# complete_system.net
KiCad netlist of a schematic drawn in EAGLE
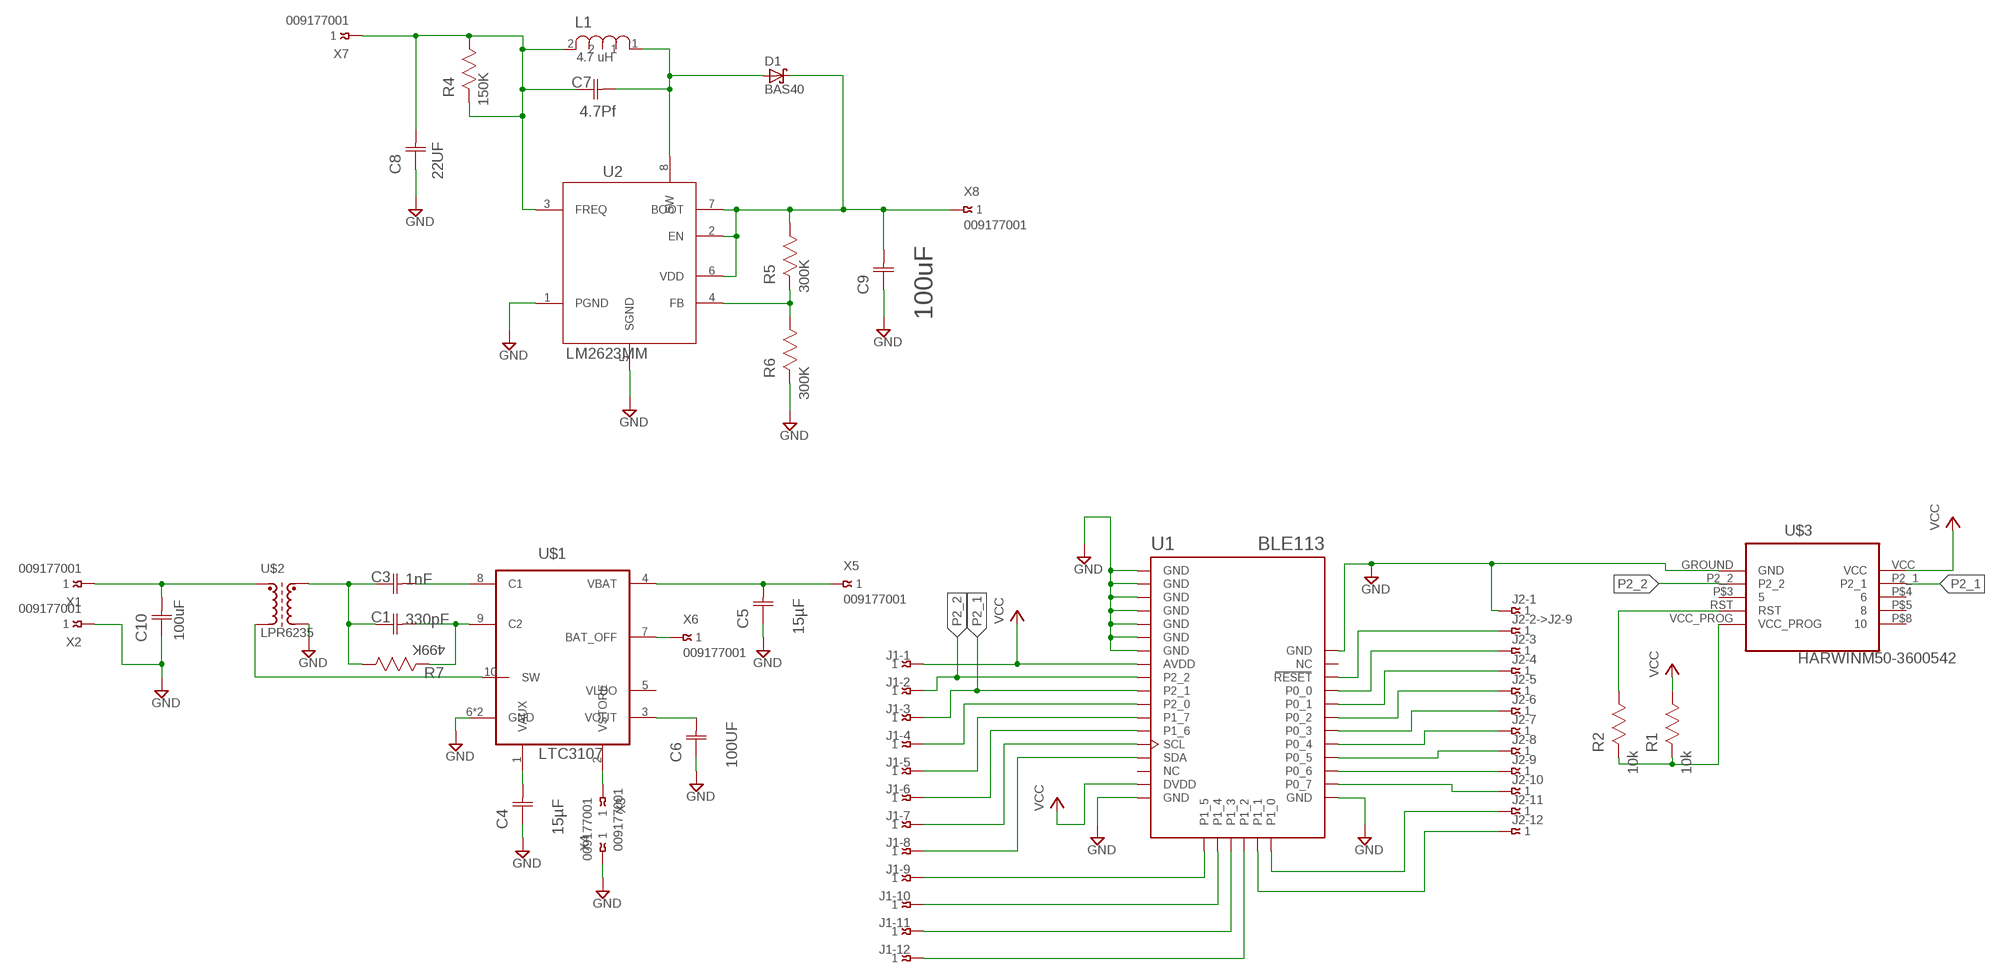
[diagram p0: schematic, sheet 1]

(export (version "E")
  (design (tool "Eeschema 10.0.6"))
  (components
    (comp (ref "C1")
      (value "330pF")
      (footprint "eagle-import:CAPC1005X60N")
      (fields (field (name "MPN") "0402YD105KAT2A") (field (name "TOLERANCE") "±10%"))
      (libsource (lib "eagle-import") (part "0402YD105KAT2A"))
    )
    (comp (ref "C3")
      (value "1nF")
      (footprint "eagle-import:CAPC1005X60N")
      (fields (field (name "MPN") "0402YD105KAT2A") (field (name "TOLERANCE") "±10%"))
      (libsource (lib "eagle-import") (part "0402YD105KAT2A"))
    )
    (comp (ref "C4")
      (value "15µF")
      (footprint "eagle-import:CAPCP3216X180N")
      (fields (field (name "MPN") "TCJA156M006R0300"))
      (libsource (lib "eagle-import") (part "TCJA156M006R0300"))
    )
    (comp (ref "C5")
      (value "15µF")
      (footprint "eagle-import:CAPCP3216X180N")
      (fields (field (name "MPN") "TCJA156M006R0300"))
      (libsource (lib "eagle-import") (part "TCJA156M006R0300"))
    )
    (comp (ref "C6")
      (value "100UF")
      (footprint "eagle-import:CAPCP3216X180N")
      (fields (field (name "MPN") "TACA107M006XTA"))
      (libsource (lib "eagle-import") (part "TACA107M006XTA"))
    )
    (comp (ref "C7")
      (value "4.7Pf")
      (footprint "eagle-import:CAPC1005X60N")
      (fields (field (name "MPN") "0402YD105KAT2A") (field (name "TOLERANCE") "±10%"))
      (libsource (lib "eagle-import") (part "0402YD105KAT2A"))
    )
    (comp (ref "C8")
      (value "22UF")
      (footprint "eagle-import:CAPC2012X94N")
      (fields (field (name "MPN") "0805YA120KAT2A") (field (name "TOLERANCE") "±10%"))
      (libsource (lib "eagle-import") (part "0805YA120KAT2A"))
    )
    (comp (ref "C9")
      (value "100uF")
      (footprint "eagle-import:CAPC3216X180N")
      (fields (field (name "MPN") "C1206C107M9PACTU") (field (name "TOLERANCE") "±20%"))
      (libsource (lib "eagle-import") (part "C1206C107M9PACTU"))
    )
    (comp (ref "C10")
      (value "100uF")
      (footprint "eagle-import:CAPC3216X180N")
      (fields (field (name "MPN") "C1206C107M9PACTU") (field (name "TOLERANCE") "±20%"))
      (libsource (lib "eagle-import") (part "C1206C107M9PACTU"))
    )
    (comp (ref "D1")
      (value "BAS40")
      (footprint "eagle-import:SOT23")
      (libsource (lib "eagle-import") (part "BAS40"))
    )
    (comp (ref "J1-1")
      (value "009177001")
      (footprint "eagle-import:009177001")
      (fields (field (name "MPN") "009177001001006"))
      (libsource (lib "eagle-import") (part "00917?0017"))
    )
    (comp (ref "J1-2")
      (value "009177001")
      (footprint "eagle-import:009177001")
      (fields (field (name "MPN") "009177001001006"))
      (libsource (lib "eagle-import") (part "00917?0017"))
    )
    (comp (ref "J1-3")
      (value "009177001")
      (footprint "eagle-import:009177001")
      (fields (field (name "MPN") "009177001001006"))
      (libsource (lib "eagle-import") (part "00917?0017"))
    )
    (comp (ref "J1-4")
      (value "009177001")
      (footprint "eagle-import:009177001")
      (fields (field (name "MPN") "009177001001006"))
      (libsource (lib "eagle-import") (part "00917?0017"))
    )
    (comp (ref "J1-5")
      (value "009177001")
      (footprint "eagle-import:009177001")
      (fields (field (name "MPN") "009177001001006"))
      (libsource (lib "eagle-import") (part "00917?0017"))
    )
    (comp (ref "J1-6")
      (value "009177001")
      (footprint "eagle-import:009177001")
      (fields (field (name "MPN") "009177001001006"))
      (libsource (lib "eagle-import") (part "00917?0017"))
    )
    (comp (ref "J1-7")
      (value "009177001")
      (footprint "eagle-import:009177001")
      (fields (field (name "MPN") "009177001001006"))
      (libsource (lib "eagle-import") (part "00917?0017"))
    )
    (comp (ref "J1-8")
      (value "009177001")
      (footprint "eagle-import:009177001")
      (fields (field (name "MPN") "009177001001006"))
      (libsource (lib "eagle-import") (part "00917?0017"))
    )
    (comp (ref "J1-9")
      (value "009177001")
      (footprint "eagle-import:009177001")
      (fields (field (name "MPN") "009177001001006"))
      (libsource (lib "eagle-import") (part "00917?0017"))
    )
    (comp (ref "J1-10")
      (value "009177001")
      (footprint "eagle-import:009177001")
      (fields (field (name "MPN") "009177001001006"))
      (libsource (lib "eagle-import") (part "00917?0017"))
    )
    (comp (ref "J1-11")
      (value "009177001")
      (footprint "eagle-import:009177001")
      (fields (field (name "MPN") "009177001001006"))
      (libsource (lib "eagle-import") (part "00917?0017"))
    )
    (comp (ref "J1-12")
      (value "009177001")
      (footprint "eagle-import:009177001")
      (fields (field (name "MPN") "009177001001006"))
      (libsource (lib "eagle-import") (part "00917?0017"))
    )
    (comp (ref "J2-1")
      (value "009177001")
      (footprint "eagle-import:009177001")
      (fields (field (name "MPN") "009177001001006"))
      (libsource (lib "eagle-import") (part "00917?0017"))
    )
    (comp (ref "J2-2->J2-9")
      (value "009177001")
      (footprint "eagle-import:009177001")
      (fields (field (name "MPN") "009177001001006"))
      (libsource (lib "eagle-import") (part "00917?0017"))
    )
    (comp (ref "J2-3")
      (value "009177001")
      (footprint "eagle-import:009177001")
      (fields (field (name "MPN") "009177001001006"))
      (libsource (lib "eagle-import") (part "00917?0017"))
    )
    (comp (ref "J2-4")
      (value "009177001")
      (footprint "eagle-import:009177001")
      (fields (field (name "MPN") "009177001001006"))
      (libsource (lib "eagle-import") (part "00917?0017"))
    )
    (comp (ref "J2-5")
      (value "009177001")
      (footprint "eagle-import:009177001")
      (fields (field (name "MPN") "009177001001006"))
      (libsource (lib "eagle-import") (part "00917?0017"))
    )
    (comp (ref "J2-6")
      (value "009177001")
      (footprint "eagle-import:009177001")
      (fields (field (name "MPN") "009177001001006"))
      (libsource (lib "eagle-import") (part "00917?0017"))
    )
    (comp (ref "J2-7")
      (value "009177001")
      (footprint "eagle-import:009177001")
      (fields (field (name "MPN") "009177001001006"))
      (libsource (lib "eagle-import") (part "00917?0017"))
    )
    (comp (ref "J2-8")
      (value "009177001")
      (footprint "eagle-import:009177001")
      (fields (field (name "MPN") "009177001001006"))
      (libsource (lib "eagle-import") (part "00917?0017"))
    )
    (comp (ref "J2-9")
      (value "009177001")
      (footprint "eagle-import:009177001")
      (fields (field (name "MPN") "009177001001006"))
      (libsource (lib "eagle-import") (part "00917?0017"))
    )
    (comp (ref "J2-10")
      (value "009177001")
      (footprint "eagle-import:009177001")
      (fields (field (name "MPN") "009177001001006"))
      (libsource (lib "eagle-import") (part "00917?0017"))
    )
    (comp (ref "J2-11")
      (value "009177001")
      (footprint "eagle-import:009177001")
      (fields (field (name "MPN") "009177001001006"))
      (libsource (lib "eagle-import") (part "00917?0017"))
    )
    (comp (ref "J2-12")
      (value "009177001")
      (footprint "eagle-import:009177001")
      (fields (field (name "MPN") "009177001001006"))
      (libsource (lib "eagle-import") (part "00917?0017"))
    )
    (comp (ref "L1")
      (value "4.7 uH")
      (footprint "eagle-import:INDC3225X22N")
      (fields (field (name "MPN") "PM1210-4R7J-RC") (field (name "TOLERANCE") "±5 %"))
      (libsource (lib "eagle-import") (part "PM1210-4R7J-RC"))
    )
    (comp (ref "R1")
      (value "10k")
      (footprint "eagle-import:RESC1005X40N")
      (fields (field (name "MPN") "CRCW0402300KFKED") (field (name "TOLERANCE") "±1%"))
      (libsource (lib "eagle-import") (part "CRCW0402300KFKED"))
    )
    (comp (ref "R2")
      (value "10k")
      (footprint "eagle-import:RESC1005X40N")
      (fields (field (name "MPN") "CRCW0402300KFKED") (field (name "TOLERANCE") "±1%"))
      (libsource (lib "eagle-import") (part "CRCW0402300KFKED"))
    )
    (comp (ref "R4")
      (value "150K")
      (footprint "eagle-import:RESC1005X40N")
      (fields (field (name "MPN") "CRCW0402150KFKED") (field (name "TOLERANCE") "±1%"))
      (libsource (lib "eagle-import") (part "CRCW0402150KFKED"))
    )
    (comp (ref "R5")
      (value "300K")
      (footprint "eagle-import:RESC1005X40N")
      (fields (field (name "MPN") "CRCW0402300KFKED") (field (name "TOLERANCE") "±1%"))
      (libsource (lib "eagle-import") (part "CRCW0402300KFKED"))
    )
    (comp (ref "R6")
      (value "300K")
      (footprint "eagle-import:RESC1005X40N")
      (fields (field (name "MPN") "CRCW0402300KFKED") (field (name "TOLERANCE") "±1%"))
      (libsource (lib "eagle-import") (part "CRCW0402300KFKED"))
    )
    (comp (ref "R7")
      (value "499K")
      (footprint "eagle-import:RESC1005X40N")
      (fields (field (name "MPN") "CRCW0402300KFKED") (field (name "TOLERANCE") "±1%"))
      (libsource (lib "eagle-import") (part "CRCW0402300KFKED"))
    )
    (comp (ref "U$1")
      (value "LTC3107")
      (footprint "eagle-import:LTC3107")
      (libsource (lib "eagle-import") (part "LTC3107"))
    )
    (comp (ref "U$2")
      (value "LPR6235")
      (footprint "eagle-import:LPR6235")
      (libsource (lib "eagle-import") (part "LPR6235"))
    )
    (comp (ref "U$3")
      (value "HARWINM50-3600542")
      (footprint "eagle-import:HARWINM50-3600542")
      (libsource (lib "eagle-import") (part "HARWINM50-3600542"))
    )
    (comp (ref "U1")
      (value "BLE113")
      (footprint "eagle-import:BLE113-A")
      (libsource (lib "eagle-import") (part "BLE113-VISUAL-A"))
    )
    (comp (ref "U2")
      (value "LM2623MM")
      (footprint "eagle-import:SOP65P490X110-8N")
      (libsource (lib "eagle-import") (part "LM2623MM"))
    )
    (comp (ref "X1")
      (value "009177001")
      (footprint "eagle-import:009177001")
      (fields (field (name "MPN") "009177001001006"))
      (libsource (lib "eagle-import") (part "00917?0017"))
    )
    (comp (ref "X2")
      (value "009177001")
      (footprint "eagle-import:009177001")
      (fields (field (name "MPN") "009177001001006"))
      (libsource (lib "eagle-import") (part "00917?0017"))
    )
    (comp (ref "X3")
      (value "009177001")
      (footprint "eagle-import:009177001")
      (fields (field (name "MPN") "009177001001006"))
      (libsource (lib "eagle-import") (part "00917?0017"))
    )
    (comp (ref "X4")
      (value "009177001")
      (footprint "eagle-import:009177001")
      (fields (field (name "MPN") "009177001001006"))
      (libsource (lib "eagle-import") (part "00917?0017"))
    )
    (comp (ref "X5")
      (value "009177001")
      (footprint "eagle-import:009177001")
      (fields (field (name "MPN") "009177001001006"))
      (libsource (lib "eagle-import") (part "00917?0017"))
    )
    (comp (ref "X6")
      (value "009177001")
      (footprint "eagle-import:009177001")
      (fields (field (name "MPN") "009177001001006"))
      (libsource (lib "eagle-import") (part "00917?0017"))
    )
    (comp (ref "X7")
      (value "009177001")
      (footprint "eagle-import:009177001")
      (fields (field (name "MPN") "009177001001006"))
      (libsource (lib "eagle-import") (part "00917?0017"))
    )
    (comp (ref "X8")
      (value "009177001")
      (footprint "eagle-import:009177001")
      (fields (field (name "MPN") "009177001001006"))
      (libsource (lib "eagle-import") (part "00917?0017"))
    )
  )
  (nets
    (net (code "1") (name "GND") (class "Default")
      (node (ref "C10") (pin "1") (pinfunction "C1_1") (pintype "passive"))
      (node (ref "C4") (pin "1") (pinfunction "C1_1") (pintype "passive"))
      (node (ref "C5") (pin "1") (pinfunction "C1_1") (pintype "passive"))
      (node (ref "C6") (pin "1") (pinfunction "C1_1") (pintype "passive"))
      (node (ref "C8") (pin "1") (pinfunction "C1_1") (pintype "passive"))
      (node (ref "C9") (pin "1") (pinfunction "C1_1") (pintype "passive"))
      (node (ref "J2-1") (pin "1") (pinfunction "1_1") (pintype "passive"))
      (node (ref "R6") (pin "2") (pinfunction "2_2") (pintype "passive"))
      (node (ref "U$1") (pin "11") (pinfunction "GND_11") (pintype "passive"))
      (node (ref "U$1") (pin "6") (pinfunction "GND_6") (pintype "passive"))
      (node (ref "U$2") (pin "P$3") (pinfunction "OP2_P$3") (pintype "passive"))
      (node (ref "U$3") (pin "GROUND") (pinfunction "GND_GROUND") (pintype "passive"))
      (node (ref "U1") (pin "GND") (pinfunction "GND_GND") (pintype "power_in"))
      (node (ref "U1") (pin "GND@10") (pinfunction "GND_GND@10") (pintype "power_in"))
      (node (ref "U1") (pin "GND@2") (pinfunction "GND_GND@2") (pintype "power_in"))
      (node (ref "U1") (pin "GND@3") (pinfunction "GND_GND@3") (pintype "power_in"))
      (node (ref "U1") (pin "GND@4") (pinfunction "GND_GND@4") (pintype "power_in"))
      (node (ref "U1") (pin "GND@5") (pinfunction "GND_GND@5") (pintype "power_in"))
      (node (ref "U1") (pin "GND@6") (pinfunction "GND_GND@6") (pintype "power_in"))
      (node (ref "U1") (pin "GND@7") (pinfunction "GND_GND@7") (pintype "power_in"))
      (node (ref "U1") (pin "GND@8") (pinfunction "GND_GND@8") (pintype "power_in"))
      (node (ref "U1") (pin "GND@9") (pinfunction "GND_GND@9") (pintype "power_in"))
      (node (ref "U2") (pin "1") (pinfunction "PGND_1") (pintype "passive"))
      (node (ref "U2") (pin "5") (pinfunction "SGND_5") (pintype "passive"))
      (node (ref "X2") (pin "1") (pinfunction "1_1") (pintype "passive"))
      (node (ref "X4") (pin "1") (pinfunction "1_1") (pintype "passive"))
    )
    (net (code "2") (name "Net-(C1-C1)") (class "Default")
      (node (ref "C1") (pin "2") (pinfunction "C1_2") (pintype "passive"))
      (node (ref "C3") (pin "2") (pinfunction "C1_2") (pintype "passive"))
      (node (ref "R7") (pin "1") (pinfunction "1_1") (pintype "passive"))
      (node (ref "U$2") (pin "P$4") (pinfunction "OP1_P$4") (pintype "passive"))
    )
    (net (code "3") (name "Net-(C1-C2)") (class "Default")
      (node (ref "C1") (pin "1") (pinfunction "C2_1") (pintype "passive"))
      (node (ref "R7") (pin "2") (pinfunction "2_2") (pintype "passive"))
      (node (ref "U$1") (pin "9") (pinfunction "C2_9") (pintype "input"))
    )
    (net (code "4") (name "Net-(C3-C2)") (class "Default")
      (node (ref "C3") (pin "1") (pinfunction "C2_1") (pintype "passive"))
      (node (ref "U$1") (pin "8") (pinfunction "C1_8") (pintype "input"))
    )
    (net (code "5") (name "Net-(C4-C2)") (class "Default")
      (node (ref "C4") (pin "2") (pinfunction "C2_2") (pintype "passive"))
      (node (ref "U$1") (pin "1") (pinfunction "VAUX_1") (pintype "input"))
    )
    (net (code "6") (name "Net-(C5-C2)") (class "Default")
      (node (ref "C5") (pin "2") (pinfunction "C2_2") (pintype "passive"))
      (node (ref "U$1") (pin "4") (pinfunction "VBAT_4") (pintype "input"))
      (node (ref "X5") (pin "1") (pinfunction "1_1") (pintype "passive"))
    )
    (net (code "7") (name "Net-(C6-C2)") (class "Default")
      (node (ref "C6") (pin "2") (pinfunction "C2_2") (pintype "passive"))
      (node (ref "U$1") (pin "3") (pinfunction "VOUT_3") (pintype "output"))
    )
    (net (code "8") (name "Net-(C7-C1)") (class "Default")
      (node (ref "C7") (pin "2") (pinfunction "C1_2") (pintype "passive"))
      (node (ref "C8") (pin "2") (pinfunction "C2_2") (pintype "passive"))
      (node (ref "L1") (pin "2") (pinfunction "2_2") (pintype "passive"))
      (node (ref "R4") (pin "1") (pinfunction "1_1") (pintype "passive"))
      (node (ref "R4") (pin "2") (pinfunction "2_2") (pintype "passive"))
      (node (ref "U2") (pin "3") (pinfunction "FREQ_3") (pintype "input"))
      (node (ref "X7") (pin "1") (pinfunction "1_1") (pintype "passive"))
    )
    (net (code "9") (name "Net-(C7-C2)") (class "Default")
      (node (ref "C7") (pin "1") (pinfunction "C2_1") (pintype "passive"))
      (node (ref "D1") (pin "1") (pinfunction "A_1") (pintype "passive"))
      (node (ref "L1") (pin "1") (pinfunction "1_1") (pintype "passive"))
      (node (ref "U2") (pin "8") (pinfunction "SW_8") (pintype "output"))
    )
    (net (code "10") (name "Net-(C9-C2)") (class "Default")
      (node (ref "C9") (pin "2") (pinfunction "C2_2") (pintype "passive"))
      (node (ref "D1") (pin "3") (pinfunction "C_3") (pintype "passive"))
      (node (ref "R5") (pin "1") (pinfunction "1_1") (pintype "passive"))
      (node (ref "U2") (pin "2") (pinfunction "EN_2") (pintype "input"))
      (node (ref "U2") (pin "6") (pinfunction "VDD_6") (pintype "power_in"))
      (node (ref "U2") (pin "7") (pinfunction "BOOT_7") (pintype "input"))
      (node (ref "X8") (pin "1") (pinfunction "1_1") (pintype "passive"))
    )
    (net (code "11") (name "Net-(C10-C2)") (class "Default")
      (node (ref "C10") (pin "2") (pinfunction "C2_2") (pintype "passive"))
      (node (ref "U$2") (pin "P$1") (pinfunction "IP1_P$1") (pintype "passive"))
      (node (ref "X1") (pin "1") (pinfunction "1_1") (pintype "passive"))
    )
    (net (code "12") (name "Net-(J1-4-Pad1)") (class "Default")
      (node (ref "J1-4") (pin "1") (pinfunction "1_1") (pintype "passive"))
      (node (ref "U1") (pin "P2_0") (pinfunction "P2_0_P2_0") (pintype "bidirectional"))
    )
    (net (code "13") (name "Net-(J1-5-Pad1)") (class "Default")
      (node (ref "J1-5") (pin "1") (pinfunction "1_1") (pintype "passive"))
      (node (ref "U1") (pin "P1_7") (pinfunction "P1_7_P1_7") (pintype "bidirectional"))
    )
    (net (code "14") (name "Net-(J1-6-Pad1)") (class "Default")
      (node (ref "J1-6") (pin "1") (pinfunction "1_1") (pintype "passive"))
      (node (ref "U1") (pin "P1_6") (pinfunction "P1_6_P1_6") (pintype "bidirectional"))
    )
    (net (code "15") (name "Net-(J1-7-Pad1)") (class "Default")
      (node (ref "J1-7") (pin "1") (pinfunction "1_1") (pintype "passive"))
      (node (ref "U1") (pin "SCL") (pinfunction "SCL_SCL") (pintype "bidirectional"))
    )
    (net (code "16") (name "Net-(J1-8-Pad1)") (class "Default")
      (node (ref "J1-8") (pin "1") (pinfunction "1_1") (pintype "passive"))
      (node (ref "U1") (pin "SDA") (pinfunction "SDA_SDA") (pintype "bidirectional"))
    )
    (net (code "17") (name "Net-(J1-9-Pad1)") (class "Default")
      (node (ref "J1-9") (pin "1") (pinfunction "1_1") (pintype "passive"))
      (node (ref "U1") (pin "P1_5") (pinfunction "P1_5_P1_5") (pintype "bidirectional"))
    )
    (net (code "18") (name "Net-(J1-10-Pad1)") (class "Default")
      (node (ref "J1-10") (pin "1") (pinfunction "1_1") (pintype "passive"))
      (node (ref "U1") (pin "P1_4") (pinfunction "P1_4_P1_4") (pintype "bidirectional"))
    )
    (net (code "19") (name "Net-(J1-11-Pad1)") (class "Default")
      (node (ref "J1-11") (pin "1") (pinfunction "1_1") (pintype "passive"))
      (node (ref "U1") (pin "P1_3") (pinfunction "P1_3_P1_3") (pintype "bidirectional"))
    )
    (net (code "20") (name "Net-(J1-12-Pad1)") (class "Default")
      (node (ref "J1-12") (pin "1") (pinfunction "1_1") (pintype "passive"))
      (node (ref "U1") (pin "P1_2") (pinfunction "P1_2_P1_2") (pintype "bidirectional"))
    )
    (net (code "21") (name "Net-(J2-2->J2-9-Pad1)") (class "Default")
      (node (ref "J2-2->J2-9") (pin "1") (pinfunction "1_1") (pintype "passive"))
      (node (ref "U1") (pin "RESET") (pinfunction "RESET_RESET") (pintype "input"))
    )
    (net (code "22") (name "Net-(J2-3-Pad1)") (class "Default")
      (node (ref "J2-3") (pin "1") (pinfunction "1_1") (pintype "passive"))
      (node (ref "U1") (pin "P0_0") (pinfunction "P0_0_P0_0") (pintype "bidirectional"))
    )
    (net (code "23") (name "Net-(J2-4-Pad1)") (class "Default")
      (node (ref "J2-4") (pin "1") (pinfunction "1_1") (pintype "passive"))
      (node (ref "U1") (pin "P0_1") (pinfunction "P0_1_P0_1") (pintype "bidirectional"))
    )
    (net (code "24") (name "Net-(J2-5-Pad1)") (class "Default")
      (node (ref "J2-5") (pin "1") (pinfunction "1_1") (pintype "passive"))
      (node (ref "U1") (pin "P0_2") (pinfunction "P0_2_P0_2") (pintype "bidirectional"))
    )
    (net (code "25") (name "Net-(J2-6-Pad1)") (class "Default")
      (node (ref "J2-6") (pin "1") (pinfunction "1_1") (pintype "passive"))
      (node (ref "U1") (pin "P0_3") (pinfunction "P0_3_P0_3") (pintype "bidirectional"))
    )
    (net (code "26") (name "Net-(J2-7-Pad1)") (class "Default")
      (node (ref "J2-7") (pin "1") (pinfunction "1_1") (pintype "passive"))
      (node (ref "U1") (pin "P0_4") (pinfunction "P0_4_P0_4") (pintype "bidirectional"))
    )
    (net (code "27") (name "Net-(J2-8-Pad1)") (class "Default")
      (node (ref "J2-8") (pin "1") (pinfunction "1_1") (pintype "passive"))
      (node (ref "U1") (pin "P0_5") (pinfunction "P0_5_P0_5") (pintype "bidirectional"))
    )
    (net (code "28") (name "Net-(J2-9-Pad1)") (class "Default")
      (node (ref "J2-9") (pin "1") (pinfunction "1_1") (pintype "passive"))
      (node (ref "U1") (pin "P0_6") (pinfunction "P0_6_P0_6") (pintype "bidirectional"))
    )
    (net (code "29") (name "Net-(J2-10-Pad1)") (class "Default")
      (node (ref "J2-10") (pin "1") (pinfunction "1_1") (pintype "passive"))
      (node (ref "U1") (pin "P0_7") (pinfunction "P0_7_P0_7") (pintype "bidirectional"))
    )
    (net (code "30") (name "Net-(J2-11-Pad1)") (class "Default")
      (node (ref "J2-11") (pin "1") (pinfunction "1_1") (pintype "passive"))
      (node (ref "U1") (pin "P1_0") (pinfunction "P1_0_P1_0") (pintype "bidirectional"))
    )
    (net (code "31") (name "Net-(J2-12-Pad1)") (class "Default")
      (node (ref "J2-12") (pin "1") (pinfunction "1_1") (pintype "passive"))
      (node (ref "U1") (pin "P1_1") (pinfunction "P1_1_P1_1") (pintype "bidirectional"))
    )
    (net (code "32") (name "Net-(R1-Pad2)") (class "Default")
      (node (ref "R1") (pin "2") (pinfunction "2_2") (pintype "passive"))
      (node (ref "R2") (pin "2") (pinfunction "2_2") (pintype "passive"))
      (node (ref "U$3") (pin "VCC_PROG") (pinfunction "VCC_PROG_VCC_PROG") (pintype "passive"))
    )
    (net (code "33") (name "Net-(R2-Pad1)") (class "Default")
      (node (ref "R2") (pin "1") (pinfunction "1_1") (pintype "passive"))
      (node (ref "U$3") (pin "RST") (pinfunction "RST_RST") (pintype "passive"))
    )
    (net (code "34") (name "Net-(U$1-BAT_OFF)") (class "Default")
      (node (ref "U$1") (pin "7") (pinfunction "BAT_OFF_7") (pintype "output"))
      (node (ref "X6") (pin "1") (pinfunction "1_1") (pintype "passive"))
    )
    (net (code "35") (name "Net-(U$1-SW)") (class "Default")
      (node (ref "U$1") (pin "10") (pinfunction "SW_10") (pintype "bidirectional"))
      (node (ref "U$2") (pin "P$2") (pinfunction "IP2_P$2") (pintype "passive"))
    )
    (net (code "36") (name "Net-(U$1-VSTORE)") (class "Default")
      (node (ref "U$1") (pin "2") (pinfunction "VSTORE_2") (pintype "output"))
      (node (ref "X3") (pin "1") (pinfunction "1_1") (pintype "passive"))
    )
    (net (code "37") (name "Net-(U2-FB)") (class "Default")
      (node (ref "R5") (pin "2") (pinfunction "2_2") (pintype "passive"))
      (node (ref "R6") (pin "1") (pinfunction "1_1") (pintype "passive"))
      (node (ref "U2") (pin "4") (pinfunction "FB_4") (pintype "input"))
    )
    (net (code "38") (name "P2_1") (class "Default")
      (node (ref "J1-3") (pin "1") (pinfunction "1_1") (pintype "passive"))
      (node (ref "U$3") (pin "P2_1") (pinfunction "P2_1_P2_1") (pintype "passive"))
      (node (ref "U1") (pin "P2_1") (pinfunction "P2_1_P2_1") (pintype "bidirectional"))
    )
    (net (code "39") (name "P2_2") (class "Default")
      (node (ref "J1-2") (pin "1") (pinfunction "1_1") (pintype "passive"))
      (node (ref "U$3") (pin "P2_2") (pinfunction "P2_2_P2_2") (pintype "passive"))
      (node (ref "U1") (pin "P2_2") (pinfunction "P2_2_P2_2") (pintype "bidirectional"))
    )
    (net (code "40") (name "VCC") (class "Default")
      (node (ref "J1-1") (pin "1") (pinfunction "1_1") (pintype "passive"))
      (node (ref "R1") (pin "1") (pinfunction "1_1") (pintype "passive"))
      (node (ref "U$3") (pin "VCC") (pinfunction "VCC_VCC") (pintype "passive"))
      (node (ref "U1") (pin "AVDD") (pinfunction "AVDD_AVDD") (pintype "power_in"))
      (node (ref "U1") (pin "DVDD") (pinfunction "DVDD_DVDD") (pintype "power_in"))
    )
    (net (code "41") (name "unconnected-(U$1-VLDO-Pad5)") (class "Default")
      (node (ref "U$1") (pin "5") (pinfunction "VLDO_5") (pintype "output"))
    )
    (net (code "42") (name "unconnected-(U$3-5-PadP$3)") (class "Default")
      (node (ref "U$3") (pin "P$3") (pinfunction "5_P$3") (pintype "no_connect"))
    )
    (net (code "43") (name "unconnected-(U$3-6-PadP$4)") (class "Default")
      (node (ref "U$3") (pin "P$4") (pinfunction "6_P$4") (pintype "no_connect"))
    )
    (net (code "44") (name "unconnected-(U$3-8-PadP$5)") (class "Default")
      (node (ref "U$3") (pin "P$5") (pinfunction "8_P$5") (pintype "no_connect"))
    )
    (net (code "45") (name "unconnected-(U$3-10-PadP$8)") (class "Default")
      (node (ref "U$3") (pin "P$8") (pinfunction "10_P$8") (pintype "no_connect"))
    )
    (net (code "46") (name "unconnected-(U1-NC-PadNC@2)") (class "Default")
      (node (ref "U1") (pin "NC@2") (pinfunction "NC_NC@2") (pintype "no_connect"))
    )
    (net (code "47") (name "unconnected-(U1-PadNC)") (class "Default")
      (node (ref "U1") (pin "NC") (pinfunction "NC_NC") (pintype "no_connect"))
    )
  )
)
